# LMG1210BOB.net
KiCad netlist of a schematic drawn in Altium Designer
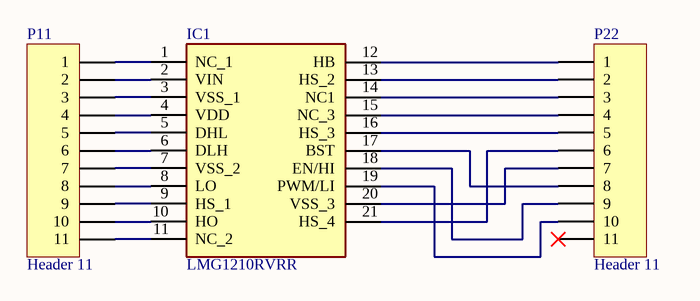
[diagram p0: LMG1210BOB.SchDoc]

(export (version "E")
  (design (tool "Eeschema 10.0.6"))
  (components
    (comp (ref "IC1")
      (value "LMG1210RVRR")
      (footprint "RcMPPTLib:LMG1210RVRR")
      (description "Integrated Circuit")
      (fields (field (name "MOUSER PART NUMBER") "595-LMG1210RVRR"))
      (libsource (lib "*") (part "LMG1210RVRR"))
    )
    (comp (ref "P11")
      (value "Header 11")
      (footprint "HDR1X11")
      (description "Header, 11-Pin")
      (fields (field (name "PUBLISHER") "Altium Limited"))
      (libsource (lib "Miscellaneous Connectors") (part "Header 11"))
    )
    (comp (ref "P22")
      (value "Header 11")
      (footprint "HDR1X11")
      (description "Header, 11-Pin")
      (fields (field (name "PUBLISHER") "Altium Limited"))
      (libsource (lib "") (part "Header 11_1"))
    )
  )
  (nets
    (net (code "1") (name "Net-(IC1-BST)") (class "Default")
      (node (ref "IC1") (pin "17") (pinfunction "BST_17") (pintype "passive"))
      (node (ref "P22") (pin "8") (pinfunction "8_8") (pintype "passive"))
    )
    (net (code "2") (name "Net-(IC1-DHL)") (class "Default")
      (node (ref "IC1") (pin "5") (pinfunction "DHL_5") (pintype "passive"))
      (node (ref "P11") (pin "5") (pinfunction "5_5") (pintype "passive"))
    )
    (net (code "3") (name "Net-(IC1-DLH)") (class "Default")
      (node (ref "IC1") (pin "6") (pinfunction "DLH_6") (pintype "passive"))
      (node (ref "P11") (pin "6") (pinfunction "6_6") (pintype "passive"))
    )
    (net (code "4") (name "Net-(IC1-EN{slash}HI)") (class "Default")
      (node (ref "IC1") (pin "18") (pinfunction "EN/HI_18") (pintype "passive"))
      (node (ref "P22") (pin "9") (pinfunction "9_9") (pintype "passive"))
    )
    (net (code "5") (name "Net-(IC1-HB)") (class "Default")
      (node (ref "IC1") (pin "12") (pinfunction "HB_12") (pintype "passive"))
      (node (ref "P22") (pin "1") (pinfunction "1_1") (pintype "passive"))
    )
    (net (code "6") (name "Net-(IC1-HO)") (class "Default")
      (node (ref "IC1") (pin "10") (pinfunction "HO_10") (pintype "passive"))
      (node (ref "P11") (pin "10") (pinfunction "10_10") (pintype "passive"))
    )
    (net (code "7") (name "Net-(IC1-HS_1)") (class "Default")
      (node (ref "IC1") (pin "9") (pinfunction "HS_1_9") (pintype "passive"))
      (node (ref "P11") (pin "9") (pinfunction "9_9") (pintype "passive"))
    )
    (net (code "8") (name "Net-(IC1-HS_2)") (class "Default")
      (node (ref "IC1") (pin "13") (pinfunction "HS_2_13") (pintype "passive"))
      (node (ref "P22") (pin "2") (pinfunction "2_2") (pintype "passive"))
    )
    (net (code "9") (name "Net-(IC1-HS_3)") (class "Default")
      (node (ref "IC1") (pin "16") (pinfunction "HS_3_16") (pintype "passive"))
      (node (ref "P22") (pin "5") (pinfunction "5_5") (pintype "passive"))
    )
    (net (code "10") (name "Net-(IC1-HS_4)") (class "Default")
      (node (ref "IC1") (pin "21") (pinfunction "HS_4_21") (pintype "passive"))
      (node (ref "P22") (pin "6") (pinfunction "6_6") (pintype "passive"))
    )
    (net (code "11") (name "Net-(IC1-LO)") (class "Default")
      (node (ref "IC1") (pin "8") (pinfunction "LO_8") (pintype "passive"))
      (node (ref "P11") (pin "8") (pinfunction "8_8") (pintype "passive"))
    )
    (net (code "12") (name "Net-(IC1-NC1)") (class "Default")
      (node (ref "IC1") (pin "14") (pinfunction "NC1_14") (pintype "passive"))
      (node (ref "P22") (pin "3") (pinfunction "3_3") (pintype "passive"))
    )
    (net (code "13") (name "Net-(IC1-NC_1)") (class "Default")
      (node (ref "IC1") (pin "1") (pinfunction "NC_1_1") (pintype "passive"))
      (node (ref "P11") (pin "1") (pinfunction "1_1") (pintype "passive"))
    )
    (net (code "14") (name "Net-(IC1-NC_2)") (class "Default")
      (node (ref "IC1") (pin "11") (pinfunction "NC_2_11") (pintype "passive"))
      (node (ref "P11") (pin "11") (pinfunction "11_11") (pintype "passive"))
    )
    (net (code "15") (name "Net-(IC1-NC_3)") (class "Default")
      (node (ref "IC1") (pin "15") (pinfunction "NC_3_15") (pintype "passive"))
      (node (ref "P22") (pin "4") (pinfunction "4_4") (pintype "passive"))
    )
    (net (code "16") (name "Net-(IC1-PWM{slash}LI)") (class "Default")
      (node (ref "IC1") (pin "19") (pinfunction "PWM/LI_19") (pintype "passive"))
      (node (ref "P22") (pin "10") (pinfunction "10_10") (pintype "passive"))
    )
    (net (code "17") (name "Net-(IC1-VDD)") (class "Default")
      (node (ref "IC1") (pin "4") (pinfunction "VDD_4") (pintype "passive"))
      (node (ref "P11") (pin "4") (pinfunction "4_4") (pintype "passive"))
    )
    (net (code "18") (name "Net-(IC1-VIN)") (class "Default")
      (node (ref "IC1") (pin "2") (pinfunction "VIN_2") (pintype "passive"))
      (node (ref "P11") (pin "2") (pinfunction "2_2") (pintype "passive"))
    )
    (net (code "19") (name "Net-(IC1-VSS_1)") (class "Default")
      (node (ref "IC1") (pin "3") (pinfunction "VSS_1_3") (pintype "passive"))
      (node (ref "P11") (pin "3") (pinfunction "3_3") (pintype "passive"))
    )
    (net (code "20") (name "Net-(IC1-VSS_2)") (class "Default")
      (node (ref "IC1") (pin "7") (pinfunction "VSS_2_7") (pintype "passive"))
      (node (ref "P11") (pin "7") (pinfunction "7_7") (pintype "passive"))
    )
    (net (code "21") (name "Net-(IC1-VSS_3)") (class "Default")
      (node (ref "IC1") (pin "20") (pinfunction "VSS_3_20") (pintype "passive"))
      (node (ref "P22") (pin "7") (pinfunction "7_7") (pintype "passive"))
    )
    (net (code "22") (name "unconnected-(P22-Pad11)") (class "Default")
      (node (ref "P22") (pin "11") (pinfunction "11_11") (pintype "passive+no_connect"))
    )
  )
)
